# SparkFun_EL_Escudo_Dos.net
KiCad netlist of a schematic drawn in EAGLE
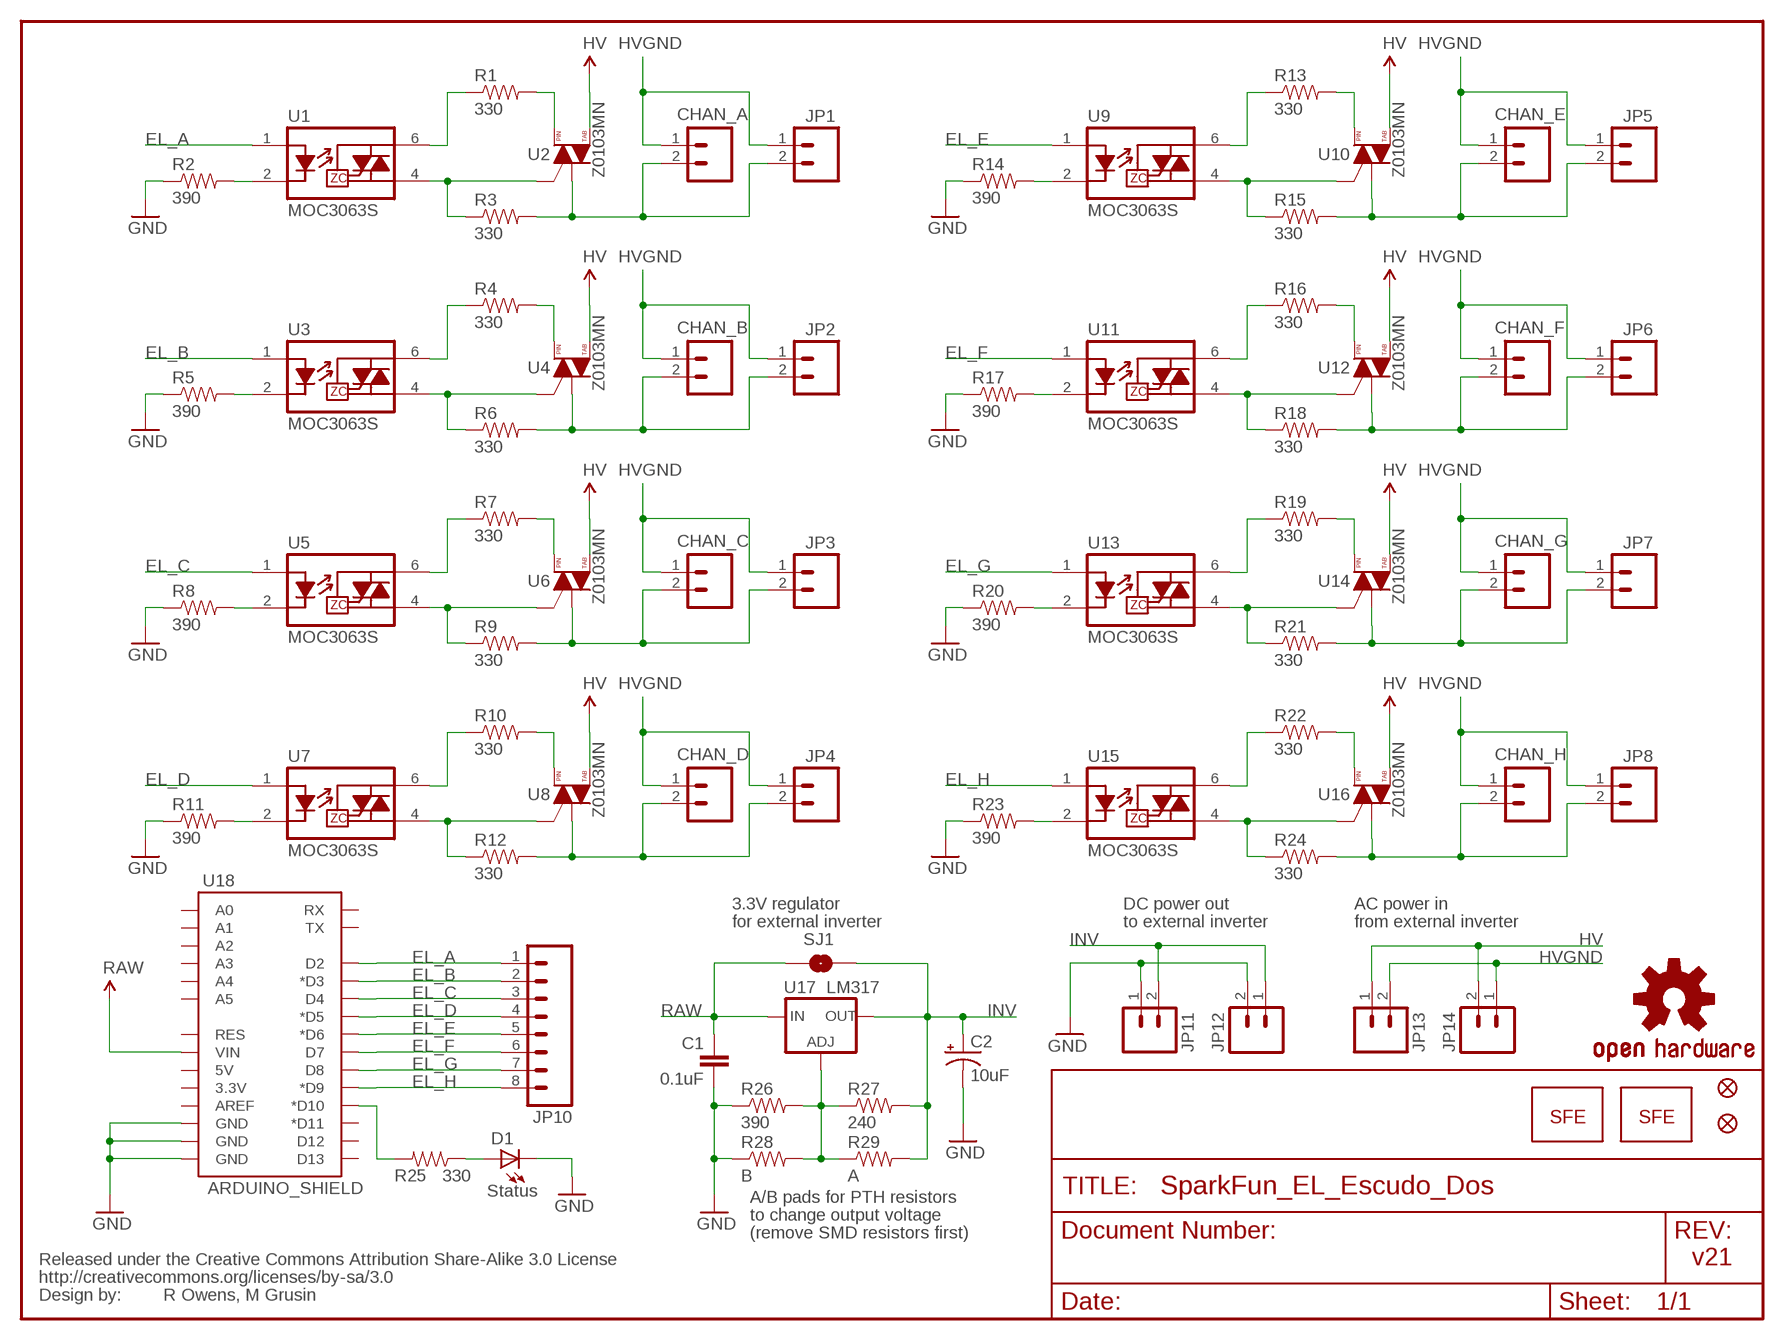
[diagram p0: schematic, sheet 1]

(export (version "E")
  (design (tool "Eeschema 10.0.6"))
  (components
    (comp (ref "C1")
      (value "0.1uF")
      (footprint "eagle-import:0603-CAP")
      (libsource (lib "eagle-import") (part "CAP0603-CAP"))
    )
    (comp (ref "C2")
      (value "10uF")
      (footprint "eagle-import:EIA3216")
      (libsource (lib "eagle-import") (part "CAP_POL1206"))
    )
    (comp (ref "CHAN_A")
      (value "M02-JST-2MM-SMT")
      (footprint "eagle-import:JST-2-SMD")
      (libsource (lib "eagle-import") (part "M02-JST-2MM-SMT"))
    )
    (comp (ref "CHAN_B")
      (value "M02-JST-2MM-SMT")
      (footprint "eagle-import:JST-2-SMD")
      (libsource (lib "eagle-import") (part "M02-JST-2MM-SMT"))
    )
    (comp (ref "CHAN_C")
      (value "M02-JST-2MM-SMT")
      (footprint "eagle-import:JST-2-SMD")
      (libsource (lib "eagle-import") (part "M02-JST-2MM-SMT"))
    )
    (comp (ref "CHAN_D")
      (value "M02-JST-2MM-SMT")
      (footprint "eagle-import:JST-2-SMD")
      (libsource (lib "eagle-import") (part "M02-JST-2MM-SMT"))
    )
    (comp (ref "CHAN_E")
      (value "M02-JST-2MM-SMT")
      (footprint "eagle-import:JST-2-SMD")
      (libsource (lib "eagle-import") (part "M02-JST-2MM-SMT"))
    )
    (comp (ref "CHAN_F")
      (value "M02-JST-2MM-SMT")
      (footprint "eagle-import:JST-2-SMD")
      (libsource (lib "eagle-import") (part "M02-JST-2MM-SMT"))
    )
    (comp (ref "CHAN_G")
      (value "M02-JST-2MM-SMT")
      (footprint "eagle-import:JST-2-SMD")
      (libsource (lib "eagle-import") (part "M02-JST-2MM-SMT"))
    )
    (comp (ref "CHAN_H")
      (value "M02-JST-2MM-SMT")
      (footprint "eagle-import:JST-2-SMD")
      (libsource (lib "eagle-import") (part "M02-JST-2MM-SMT"))
    )
    (comp (ref "D1")
      (value "Status")
      (footprint "eagle-import:LED-0603")
      (libsource (lib "eagle-import") (part "LED0603"))
    )
    (comp (ref "JP1")
      (value "M02PTH")
      (footprint "eagle-import:1X02")
      (libsource (lib "eagle-import") (part "M02PTH"))
    )
    (comp (ref "JP2")
      (value "M02PTH")
      (footprint "eagle-import:1X02")
      (libsource (lib "eagle-import") (part "M02PTH"))
    )
    (comp (ref "JP3")
      (value "M02PTH")
      (footprint "eagle-import:1X02")
      (libsource (lib "eagle-import") (part "M02PTH"))
    )
    (comp (ref "JP4")
      (value "M02PTH")
      (footprint "eagle-import:1X02")
      (libsource (lib "eagle-import") (part "M02PTH"))
    )
    (comp (ref "JP5")
      (value "M02PTH")
      (footprint "eagle-import:1X02")
      (libsource (lib "eagle-import") (part "M02PTH"))
    )
    (comp (ref "JP6")
      (value "M02PTH")
      (footprint "eagle-import:1X02")
      (libsource (lib "eagle-import") (part "M02PTH"))
    )
    (comp (ref "JP7")
      (value "M02PTH")
      (footprint "eagle-import:1X02")
      (libsource (lib "eagle-import") (part "M02PTH"))
    )
    (comp (ref "JP8")
      (value "M02PTH")
      (footprint "eagle-import:1X02")
      (libsource (lib "eagle-import") (part "M02PTH"))
    )
    (comp (ref "JP9")
      (value "LOGO-SFENEW")
      (footprint "eagle-import:SFE-NEW-WEBLOGO")
      (libsource (lib "eagle-import") (part "LOGO-SFENEW"))
    )
    (comp (ref "JP10")
      (value "M081X08")
      (footprint "eagle-import:1X08")
      (libsource (lib "eagle-import") (part "M081X08"))
    )
    (comp (ref "JP11")
      (value "M02-JST-2MM-SMT")
      (footprint "eagle-import:JST-2-SMD")
      (libsource (lib "eagle-import") (part "M02-JST-2MM-SMT"))
    )
    (comp (ref "JP12")
      (value "M02PTH")
      (footprint "eagle-import:1X02")
      (libsource (lib "eagle-import") (part "M02PTH"))
    )
    (comp (ref "JP13")
      (value "M02PTH")
      (footprint "eagle-import:1X02")
      (libsource (lib "eagle-import") (part "M02PTH"))
    )
    (comp (ref "JP14")
      (value "M02-JST-2MM-SMT")
      (footprint "eagle-import:JST-2-SMD")
      (libsource (lib "eagle-import") (part "M02-JST-2MM-SMT"))
    )
    (comp (ref "JP15")
      (value "LOGO-SFENEW")
      (footprint "eagle-import:SFE-NEW-WEBLOGO")
      (libsource (lib "eagle-import") (part "LOGO-SFENEW"))
    )
    (comp (ref "JP16")
      (value "FIDUCIALUFIDUCIAL")
      (footprint "eagle-import:MICRO-FIDUCIAL")
      (libsource (lib "eagle-import") (part "FIDUCIALUFIDUCIAL"))
    )
    (comp (ref "JP17")
      (value "FIDUCIALUFIDUCIAL")
      (footprint "eagle-import:MICRO-FIDUCIAL")
      (libsource (lib "eagle-import") (part "FIDUCIALUFIDUCIAL"))
    )
    (comp (ref "R1")
      (value "330")
      (footprint "eagle-import:0603-RES")
      (libsource (lib "eagle-import") (part "RESISTOR0603-RES"))
    )
    (comp (ref "R2")
      (value "390")
      (footprint "eagle-import:0603-RES")
      (libsource (lib "eagle-import") (part "RESISTOR0603-RES"))
    )
    (comp (ref "R3")
      (value "330")
      (footprint "eagle-import:0603-RES")
      (libsource (lib "eagle-import") (part "RESISTOR0603-RES"))
    )
    (comp (ref "R4")
      (value "330")
      (footprint "eagle-import:0603-RES")
      (libsource (lib "eagle-import") (part "RESISTOR0603-RES"))
    )
    (comp (ref "R5")
      (value "390")
      (footprint "eagle-import:0603-RES")
      (libsource (lib "eagle-import") (part "RESISTOR0603-RES"))
    )
    (comp (ref "R6")
      (value "330")
      (footprint "eagle-import:0603-RES")
      (libsource (lib "eagle-import") (part "RESISTOR0603-RES"))
    )
    (comp (ref "R7")
      (value "330")
      (footprint "eagle-import:0603-RES")
      (libsource (lib "eagle-import") (part "RESISTOR0603-RES"))
    )
    (comp (ref "R8")
      (value "390")
      (footprint "eagle-import:0603-RES")
      (libsource (lib "eagle-import") (part "RESISTOR0603-RES"))
    )
    (comp (ref "R9")
      (value "330")
      (footprint "eagle-import:0603-RES")
      (libsource (lib "eagle-import") (part "RESISTOR0603-RES"))
    )
    (comp (ref "R10")
      (value "330")
      (footprint "eagle-import:0603-RES")
      (libsource (lib "eagle-import") (part "RESISTOR0603-RES"))
    )
    (comp (ref "R11")
      (value "390")
      (footprint "eagle-import:0603-RES")
      (libsource (lib "eagle-import") (part "RESISTOR0603-RES"))
    )
    (comp (ref "R12")
      (value "330")
      (footprint "eagle-import:0603-RES")
      (libsource (lib "eagle-import") (part "RESISTOR0603-RES"))
    )
    (comp (ref "R13")
      (value "330")
      (footprint "eagle-import:0603-RES")
      (libsource (lib "eagle-import") (part "RESISTOR0603-RES"))
    )
    (comp (ref "R14")
      (value "390")
      (footprint "eagle-import:0603-RES")
      (libsource (lib "eagle-import") (part "RESISTOR0603-RES"))
    )
    (comp (ref "R15")
      (value "330")
      (footprint "eagle-import:0603-RES")
      (libsource (lib "eagle-import") (part "RESISTOR0603-RES"))
    )
    (comp (ref "R16")
      (value "330")
      (footprint "eagle-import:0603-RES")
      (libsource (lib "eagle-import") (part "RESISTOR0603-RES"))
    )
    (comp (ref "R17")
      (value "390")
      (footprint "eagle-import:0603-RES")
      (libsource (lib "eagle-import") (part "RESISTOR0603-RES"))
    )
    (comp (ref "R18")
      (value "330")
      (footprint "eagle-import:0603-RES")
      (libsource (lib "eagle-import") (part "RESISTOR0603-RES"))
    )
    (comp (ref "R19")
      (value "330")
      (footprint "eagle-import:0603-RES")
      (libsource (lib "eagle-import") (part "RESISTOR0603-RES"))
    )
    (comp (ref "R20")
      (value "390")
      (footprint "eagle-import:0603-RES")
      (libsource (lib "eagle-import") (part "RESISTOR0603-RES"))
    )
    (comp (ref "R21")
      (value "330")
      (footprint "eagle-import:0603-RES")
      (libsource (lib "eagle-import") (part "RESISTOR0603-RES"))
    )
    (comp (ref "R22")
      (value "330")
      (footprint "eagle-import:0603-RES")
      (libsource (lib "eagle-import") (part "RESISTOR0603-RES"))
    )
    (comp (ref "R23")
      (value "390")
      (footprint "eagle-import:0603-RES")
      (libsource (lib "eagle-import") (part "RESISTOR0603-RES"))
    )
    (comp (ref "R24")
      (value "330")
      (footprint "eagle-import:0603-RES")
      (libsource (lib "eagle-import") (part "RESISTOR0603-RES"))
    )
    (comp (ref "R25")
      (value "330")
      (footprint "eagle-import:0603-RES")
      (libsource (lib "eagle-import") (part "RESISTOR0603-RES"))
    )
    (comp (ref "R26")
      (value "390")
      (footprint "eagle-import:0603-RES")
      (libsource (lib "eagle-import") (part "RESISTOR0603-RES"))
    )
    (comp (ref "R27")
      (value "240")
      (footprint "eagle-import:0603-RES")
      (libsource (lib "eagle-import") (part "RESISTOR0603-RES"))
    )
    (comp (ref "R28")
      (value "B")
      (footprint "eagle-import:AXIAL-0.4")
      (libsource (lib "eagle-import") (part "RESISTORPTH-1/4W"))
    )
    (comp (ref "R29")
      (value "A")
      (footprint "eagle-import:AXIAL-0.4")
      (libsource (lib "eagle-import") (part "RESISTORPTH-1/4W"))
    )
    (comp (ref "SJ1")
      (value "SOLDERJUMPERNO")
      (footprint "eagle-import:SJ_2S-NO")
      (libsource (lib "eagle-import") (part "SOLDERJUMPERNO"))
    )
    (comp (ref "U$4")
      (value "CREATIVE_COMMONS")
      (footprint "eagle-import:CREATIVE_COMMONS")
      (libsource (lib "eagle-import") (part "CREATIVE_COMMONS"))
    )
    (comp (ref "U$5")
      (value "OSHW-LOGOS")
      (footprint "eagle-import:OSHW-LOGO-S")
      (libsource (lib "eagle-import") (part "OSHW-LOGOS"))
    )
    (comp (ref "U1")
      (value "MOC3063S")
      (footprint "eagle-import:DIP8SMD")
      (libsource (lib "eagle-import") (part "MOC3063S"))
    )
    (comp (ref "U2")
      (value "Z0103MN")
      (footprint "eagle-import:SOT223")
      (libsource (lib "eagle-import") (part "TRIACSMD"))
    )
    (comp (ref "U3")
      (value "MOC3063S")
      (footprint "eagle-import:DIP8SMD")
      (libsource (lib "eagle-import") (part "MOC3063S"))
    )
    (comp (ref "U4")
      (value "Z0103MN")
      (footprint "eagle-import:SOT223")
      (libsource (lib "eagle-import") (part "TRIACSMD"))
    )
    (comp (ref "U5")
      (value "MOC3063S")
      (footprint "eagle-import:DIP8SMD")
      (libsource (lib "eagle-import") (part "MOC3063S"))
    )
    (comp (ref "U6")
      (value "Z0103MN")
      (footprint "eagle-import:SOT223")
      (libsource (lib "eagle-import") (part "TRIACSMD"))
    )
    (comp (ref "U7")
      (value "MOC3063S")
      (footprint "eagle-import:DIP8SMD")
      (libsource (lib "eagle-import") (part "MOC3063S"))
    )
    (comp (ref "U8")
      (value "Z0103MN")
      (footprint "eagle-import:SOT223")
      (libsource (lib "eagle-import") (part "TRIACSMD"))
    )
    (comp (ref "U9")
      (value "MOC3063S")
      (footprint "eagle-import:DIP8SMD")
      (libsource (lib "eagle-import") (part "MOC3063S"))
    )
    (comp (ref "U10")
      (value "Z0103MN")
      (footprint "eagle-import:SOT223")
      (libsource (lib "eagle-import") (part "TRIACSMD"))
    )
    (comp (ref "U11")
      (value "MOC3063S")
      (footprint "eagle-import:DIP8SMD")
      (libsource (lib "eagle-import") (part "MOC3063S"))
    )
    (comp (ref "U12")
      (value "Z0103MN")
      (footprint "eagle-import:SOT223")
      (libsource (lib "eagle-import") (part "TRIACSMD"))
    )
    (comp (ref "U13")
      (value "MOC3063S")
      (footprint "eagle-import:DIP8SMD")
      (libsource (lib "eagle-import") (part "MOC3063S"))
    )
    (comp (ref "U14")
      (value "Z0103MN")
      (footprint "eagle-import:SOT223")
      (libsource (lib "eagle-import") (part "TRIACSMD"))
    )
    (comp (ref "U15")
      (value "MOC3063S")
      (footprint "eagle-import:DIP8SMD")
      (libsource (lib "eagle-import") (part "MOC3063S"))
    )
    (comp (ref "U16")
      (value "Z0103MN")
      (footprint "eagle-import:SOT223")
      (libsource (lib "eagle-import") (part "TRIACSMD"))
    )
    (comp (ref "U17")
      (value "LM317")
      (footprint "eagle-import:V-REG_DPACK")
      (libsource (lib "eagle-import") (part "V_REG_317DPACK"))
    )
    (comp (ref "U18")
      (value "ARDUINO_SHIELD")
      (footprint "eagle-import:DUEMILANOVE_SHIELD_NOLABELS")
      (libsource (lib "eagle-import") (part "ARDUINO_SHIELDNOLABELS"))
    )
  )
  (nets
    (net (code "1") (name "/EL_A") (class "Default")
      (node (ref "JP10") (pin "1") (pinfunction "1_1") (pintype "passive"))
      (node (ref "U1") (pin "1") (pinfunction "A_1") (pintype "bidirectional"))
      (node (ref "U18") (pin "D2") (pinfunction "D2_D2") (pintype "bidirectional"))
    )
    (net (code "2") (name "/EL_B") (class "Default")
      (node (ref "JP10") (pin "2") (pinfunction "2_2") (pintype "passive"))
      (node (ref "U18") (pin "D3") (pinfunction "*D3_D3") (pintype "bidirectional"))
      (node (ref "U3") (pin "1") (pinfunction "A_1") (pintype "bidirectional"))
    )
    (net (code "3") (name "/EL_C") (class "Default")
      (node (ref "JP10") (pin "3") (pinfunction "3_3") (pintype "passive"))
      (node (ref "U18") (pin "D4") (pinfunction "D4_D4") (pintype "bidirectional"))
      (node (ref "U5") (pin "1") (pinfunction "A_1") (pintype "bidirectional"))
    )
    (net (code "4") (name "/EL_D") (class "Default")
      (node (ref "JP10") (pin "4") (pinfunction "4_4") (pintype "passive"))
      (node (ref "U18") (pin "D5") (pinfunction "*D5_D5") (pintype "bidirectional"))
      (node (ref "U7") (pin "1") (pinfunction "A_1") (pintype "bidirectional"))
    )
    (net (code "5") (name "/EL_E") (class "Default")
      (node (ref "JP10") (pin "5") (pinfunction "5_5") (pintype "passive"))
      (node (ref "U18") (pin "D6") (pinfunction "*D6_D6") (pintype "bidirectional"))
      (node (ref "U9") (pin "1") (pinfunction "A_1") (pintype "bidirectional"))
    )
    (net (code "6") (name "/EL_F") (class "Default")
      (node (ref "JP10") (pin "6") (pinfunction "6_6") (pintype "passive"))
      (node (ref "U11") (pin "1") (pinfunction "A_1") (pintype "bidirectional"))
      (node (ref "U18") (pin "D7") (pinfunction "D7_D7") (pintype "bidirectional"))
    )
    (net (code "7") (name "/EL_G") (class "Default")
      (node (ref "JP10") (pin "7") (pinfunction "7_7") (pintype "passive"))
      (node (ref "U13") (pin "1") (pinfunction "A_1") (pintype "bidirectional"))
      (node (ref "U18") (pin "D8") (pinfunction "D8_D8") (pintype "bidirectional"))
    )
    (net (code "8") (name "/EL_H") (class "Default")
      (node (ref "JP10") (pin "8") (pinfunction "8_8") (pintype "passive"))
      (node (ref "U15") (pin "1") (pinfunction "A_1") (pintype "bidirectional"))
      (node (ref "U18") (pin "D9") (pinfunction "*D9_D9") (pintype "bidirectional"))
    )
    (net (code "9") (name "/HVGND") (class "Default")
      (node (ref "CHAN_A") (pin "1") (pinfunction "1_1") (pintype "passive"))
      (node (ref "CHAN_B") (pin "1") (pinfunction "1_1") (pintype "passive"))
      (node (ref "CHAN_C") (pin "1") (pinfunction "1_1") (pintype "passive"))
      (node (ref "CHAN_D") (pin "1") (pinfunction "1_1") (pintype "passive"))
      (node (ref "CHAN_E") (pin "1") (pinfunction "1_1") (pintype "passive"))
      (node (ref "CHAN_F") (pin "1") (pinfunction "1_1") (pintype "passive"))
      (node (ref "CHAN_G") (pin "1") (pinfunction "1_1") (pintype "passive"))
      (node (ref "CHAN_H") (pin "1") (pinfunction "1_1") (pintype "passive"))
      (node (ref "JP1") (pin "1") (pinfunction "1_1") (pintype "passive"))
      (node (ref "JP13") (pin "2") (pinfunction "2_2") (pintype "passive"))
      (node (ref "JP14") (pin "1") (pinfunction "1_1") (pintype "passive"))
      (node (ref "JP2") (pin "1") (pinfunction "1_1") (pintype "passive"))
      (node (ref "JP3") (pin "1") (pinfunction "1_1") (pintype "passive"))
      (node (ref "JP4") (pin "1") (pinfunction "1_1") (pintype "passive"))
      (node (ref "JP5") (pin "1") (pinfunction "1_1") (pintype "passive"))
      (node (ref "JP6") (pin "1") (pinfunction "1_1") (pintype "passive"))
      (node (ref "JP7") (pin "1") (pinfunction "1_1") (pintype "passive"))
      (node (ref "JP8") (pin "1") (pinfunction "1_1") (pintype "passive"))
    )
    (net (code "10") (name "/INV") (class "Default")
      (node (ref "C2") (pin "A") (pinfunction "+_A") (pintype "passive"))
      (node (ref "JP11") (pin "2") (pinfunction "2_2") (pintype "passive"))
      (node (ref "JP12") (pin "1") (pinfunction "1_1") (pintype "passive"))
      (node (ref "R27") (pin "2") (pinfunction "2_2") (pintype "passive"))
      (node (ref "R29") (pin "P$2") (pinfunction "2_P$2") (pintype "passive"))
      (node (ref "SJ1") (pin "2") (pinfunction "2_2") (pintype "passive"))
      (node (ref "U17") (pin "4") (pinfunction "OUT_4") (pintype "output"))
    )
    (net (code "11") (name "GND") (class "Default")
      (node (ref "C1") (pin "2") (pinfunction "2_2") (pintype "passive"))
      (node (ref "C2") (pin "C") (pinfunction "-_C") (pintype "passive"))
      (node (ref "D1") (pin "C") (pinfunction "C_C") (pintype "passive"))
      (node (ref "JP11") (pin "1") (pinfunction "1_1") (pintype "passive"))
      (node (ref "JP12") (pin "2") (pinfunction "2_2") (pintype "passive"))
      (node (ref "R11") (pin "1") (pinfunction "1_1") (pintype "passive"))
      (node (ref "R14") (pin "1") (pinfunction "1_1") (pintype "passive"))
      (node (ref "R17") (pin "1") (pinfunction "1_1") (pintype "passive"))
      (node (ref "R2") (pin "1") (pinfunction "1_1") (pintype "passive"))
      (node (ref "R20") (pin "1") (pinfunction "1_1") (pintype "passive"))
      (node (ref "R23") (pin "1") (pinfunction "1_1") (pintype "passive"))
      (node (ref "R26") (pin "1") (pinfunction "1_1") (pintype "passive"))
      (node (ref "R28") (pin "P$1") (pinfunction "1_P$1") (pintype "passive"))
      (node (ref "R5") (pin "1") (pinfunction "1_1") (pintype "passive"))
      (node (ref "R8") (pin "1") (pinfunction "1_1") (pintype "passive"))
      (node (ref "U18") (pin "GND@0") (pinfunction "GND_GND@0") (pintype "bidirectional"))
      (node (ref "U18") (pin "GND@1") (pinfunction "GND_GND@1") (pintype "bidirectional"))
      (node (ref "U18") (pin "GND@2") (pinfunction "GND_GND@2") (pintype "bidirectional"))
    )
    (net (code "12") (name "HV") (class "Default")
      (node (ref "JP13") (pin "1") (pinfunction "1_1") (pintype "passive"))
      (node (ref "JP14") (pin "2") (pinfunction "2_2") (pintype "passive"))
      (node (ref "U10") (pin "4") (pinfunction "T2_4") (pintype "passive"))
      (node (ref "U12") (pin "4") (pinfunction "T2_4") (pintype "passive"))
      (node (ref "U14") (pin "4") (pinfunction "T2_4") (pintype "passive"))
      (node (ref "U16") (pin "4") (pinfunction "T2_4") (pintype "passive"))
      (node (ref "U2") (pin "4") (pinfunction "T2_4") (pintype "passive"))
      (node (ref "U4") (pin "4") (pinfunction "T2_4") (pintype "passive"))
      (node (ref "U6") (pin "4") (pinfunction "T2_4") (pintype "passive"))
      (node (ref "U8") (pin "4") (pinfunction "T2_4") (pintype "passive"))
    )
    (net (code "13") (name "Net-(D1-PadA)") (class "Default")
      (node (ref "D1") (pin "A") (pinfunction "A_A") (pintype "passive"))
      (node (ref "R25") (pin "1") (pinfunction "1_1") (pintype "passive"))
    )
    (net (code "14") (name "Net-(R1-Pad2)") (class "Default")
      (node (ref "R1") (pin "2") (pinfunction "2_2") (pintype "passive"))
      (node (ref "U2") (pin "2") (pinfunction "T2_2") (pintype "passive"))
    )
    (net (code "15") (name "Net-(R4-Pad2)") (class "Default")
      (node (ref "R4") (pin "2") (pinfunction "2_2") (pintype "passive"))
      (node (ref "U4") (pin "2") (pinfunction "T2_2") (pintype "passive"))
    )
    (net (code "16") (name "Net-(R7-Pad2)") (class "Default")
      (node (ref "R7") (pin "2") (pinfunction "2_2") (pintype "passive"))
      (node (ref "U6") (pin "2") (pinfunction "T2_2") (pintype "passive"))
    )
    (net (code "17") (name "Net-(R10-Pad2)") (class "Default")
      (node (ref "R10") (pin "2") (pinfunction "2_2") (pintype "passive"))
      (node (ref "U8") (pin "2") (pinfunction "T2_2") (pintype "passive"))
    )
    (net (code "18") (name "Net-(R13-Pad2)") (class "Default")
      (node (ref "R13") (pin "2") (pinfunction "2_2") (pintype "passive"))
      (node (ref "U10") (pin "2") (pinfunction "T2_2") (pintype "passive"))
    )
    (net (code "19") (name "Net-(R16-Pad2)") (class "Default")
      (node (ref "R16") (pin "2") (pinfunction "2_2") (pintype "passive"))
      (node (ref "U12") (pin "2") (pinfunction "T2_2") (pintype "passive"))
    )
    (net (code "20") (name "Net-(R19-Pad2)") (class "Default")
      (node (ref "R19") (pin "2") (pinfunction "2_2") (pintype "passive"))
      (node (ref "U14") (pin "2") (pinfunction "T2_2") (pintype "passive"))
    )
    (net (code "21") (name "Net-(R22-Pad2)") (class "Default")
      (node (ref "R22") (pin "2") (pinfunction "2_2") (pintype "passive"))
      (node (ref "U16") (pin "2") (pinfunction "T2_2") (pintype "passive"))
    )
    (net (code "22") (name "Net-(R28-2)") (class "Default")
      (node (ref "R26") (pin "2") (pinfunction "2_2") (pintype "passive"))
      (node (ref "R27") (pin "1") (pinfunction "1_1") (pintype "passive"))
      (node (ref "R28") (pin "P$2") (pinfunction "2_P$2") (pintype "passive"))
      (node (ref "R29") (pin "P$1") (pinfunction "1_P$1") (pintype "passive"))
      (node (ref "U17") (pin "1") (pinfunction "ADJ_1") (pintype "input"))
    )
    (net (code "23") (name "Net-(U1-K)") (class "Default")
      (node (ref "R2") (pin "2") (pinfunction "2_2") (pintype "passive"))
      (node (ref "U1") (pin "2") (pinfunction "K_2") (pintype "bidirectional"))
    )
    (net (code "24") (name "Net-(U1-T1)") (class "Default")
      (node (ref "R1") (pin "1") (pinfunction "1_1") (pintype "passive"))
      (node (ref "U1") (pin "6") (pinfunction "T1_6") (pintype "bidirectional"))
    )
    (net (code "25") (name "Net-(U1-T2)") (class "Default")
      (node (ref "R3") (pin "1") (pinfunction "1_1") (pintype "passive"))
      (node (ref "U1") (pin "4") (pinfunction "T2_4") (pintype "bidirectional"))
      (node (ref "U2") (pin "3") (pinfunction "G_3") (pintype "bidirectional"))
    )
    (net (code "26") (name "Net-(U2-T1)") (class "Default")
      (node (ref "CHAN_A") (pin "2") (pinfunction "2_2") (pintype "passive"))
      (node (ref "JP1") (pin "2") (pinfunction "2_2") (pintype "passive"))
      (node (ref "R3") (pin "2") (pinfunction "2_2") (pintype "passive"))
      (node (ref "U2") (pin "1") (pinfunction "T1_1") (pintype "bidirectional"))
    )
    (net (code "27") (name "Net-(U3-K)") (class "Default")
      (node (ref "R5") (pin "2") (pinfunction "2_2") (pintype "passive"))
      (node (ref "U3") (pin "2") (pinfunction "K_2") (pintype "bidirectional"))
    )
    (net (code "28") (name "Net-(U3-T1)") (class "Default")
      (node (ref "R4") (pin "1") (pinfunction "1_1") (pintype "passive"))
      (node (ref "U3") (pin "6") (pinfunction "T1_6") (pintype "bidirectional"))
    )
    (net (code "29") (name "Net-(U3-T2)") (class "Default")
      (node (ref "R6") (pin "1") (pinfunction "1_1") (pintype "passive"))
      (node (ref "U3") (pin "4") (pinfunction "T2_4") (pintype "bidirectional"))
      (node (ref "U4") (pin "3") (pinfunction "G_3") (pintype "bidirectional"))
    )
    (net (code "30") (name "Net-(U4-T1)") (class "Default")
      (node (ref "CHAN_B") (pin "2") (pinfunction "2_2") (pintype "passive"))
      (node (ref "JP2") (pin "2") (pinfunction "2_2") (pintype "passive"))
      (node (ref "R6") (pin "2") (pinfunction "2_2") (pintype "passive"))
      (node (ref "U4") (pin "1") (pinfunction "T1_1") (pintype "bidirectional"))
    )
    (net (code "31") (name "Net-(U5-K)") (class "Default")
      (node (ref "R8") (pin "2") (pinfunction "2_2") (pintype "passive"))
      (node (ref "U5") (pin "2") (pinfunction "K_2") (pintype "bidirectional"))
    )
    (net (code "32") (name "Net-(U5-T1)") (class "Default")
      (node (ref "R7") (pin "1") (pinfunction "1_1") (pintype "passive"))
      (node (ref "U5") (pin "6") (pinfunction "T1_6") (pintype "bidirectional"))
    )
    (net (code "33") (name "Net-(U5-T2)") (class "Default")
      (node (ref "R9") (pin "1") (pinfunction "1_1") (pintype "passive"))
      (node (ref "U5") (pin "4") (pinfunction "T2_4") (pintype "bidirectional"))
      (node (ref "U6") (pin "3") (pinfunction "G_3") (pintype "bidirectional"))
    )
    (net (code "34") (name "Net-(U6-T1)") (class "Default")
      (node (ref "CHAN_C") (pin "2") (pinfunction "2_2") (pintype "passive"))
      (node (ref "JP3") (pin "2") (pinfunction "2_2") (pintype "passive"))
      (node (ref "R9") (pin "2") (pinfunction "2_2") (pintype "passive"))
      (node (ref "U6") (pin "1") (pinfunction "T1_1") (pintype "bidirectional"))
    )
    (net (code "35") (name "Net-(U7-K)") (class "Default")
      (node (ref "R11") (pin "2") (pinfunction "2_2") (pintype "passive"))
      (node (ref "U7") (pin "2") (pinfunction "K_2") (pintype "bidirectional"))
    )
    (net (code "36") (name "Net-(U7-T1)") (class "Default")
      (node (ref "R10") (pin "1") (pinfunction "1_1") (pintype "passive"))
      (node (ref "U7") (pin "6") (pinfunction "T1_6") (pintype "bidirectional"))
    )
    (net (code "37") (name "Net-(U7-T2)") (class "Default")
      (node (ref "R12") (pin "1") (pinfunction "1_1") (pintype "passive"))
      (node (ref "U7") (pin "4") (pinfunction "T2_4") (pintype "bidirectional"))
      (node (ref "U8") (pin "3") (pinfunction "G_3") (pintype "bidirectional"))
    )
    (net (code "38") (name "Net-(U8-T1)") (class "Default")
      (node (ref "CHAN_D") (pin "2") (pinfunction "2_2") (pintype "passive"))
      (node (ref "JP4") (pin "2") (pinfunction "2_2") (pintype "passive"))
      (node (ref "R12") (pin "2") (pinfunction "2_2") (pintype "passive"))
      (node (ref "U8") (pin "1") (pinfunction "T1_1") (pintype "bidirectional"))
    )
    (net (code "39") (name "Net-(U9-K)") (class "Default")
      (node (ref "R14") (pin "2") (pinfunction "2_2") (pintype "passive"))
      (node (ref "U9") (pin "2") (pinfunction "K_2") (pintype "bidirectional"))
    )
    (net (code "40") (name "Net-(U9-T1)") (class "Default")
      (node (ref "R13") (pin "1") (pinfunction "1_1") (pintype "passive"))
      (node (ref "U9") (pin "6") (pinfunction "T1_6") (pintype "bidirectional"))
    )
    (net (code "41") (name "Net-(U10-G)") (class "Default")
      (node (ref "R15") (pin "1") (pinfunction "1_1") (pintype "passive"))
      (node (ref "U10") (pin "3") (pinfunction "G_3") (pintype "bidirectional"))
      (node (ref "U9") (pin "4") (pinfunction "T2_4") (pintype "bidirectional"))
    )
    (net (code "42") (name "Net-(U10-T1)") (class "Default")
      (node (ref "CHAN_E") (pin "2") (pinfunction "2_2") (pintype "passive"))
      (node (ref "JP5") (pin "2") (pinfunction "2_2") (pintype "passive"))
      (node (ref "R15") (pin "2") (pinfunction "2_2") (pintype "passive"))
      (node (ref "U10") (pin "1") (pinfunction "T1_1") (pintype "bidirectional"))
    )
    (net (code "43") (name "Net-(U11-K)") (class "Default")
      (node (ref "R17") (pin "2") (pinfunction "2_2") (pintype "passive"))
      (node (ref "U11") (pin "2") (pinfunction "K_2") (pintype "bidirectional"))
    )
    (net (code "44") (name "Net-(U11-T1)") (class "Default")
      (node (ref "R16") (pin "1") (pinfunction "1_1") (pintype "passive"))
      (node (ref "U11") (pin "6") (pinfunction "T1_6") (pintype "bidirectional"))
    )
    (net (code "45") (name "Net-(U11-T2)") (class "Default")
      (node (ref "R18") (pin "1") (pinfunction "1_1") (pintype "passive"))
      (node (ref "U11") (pin "4") (pinfunction "T2_4") (pintype "bidirectional"))
      (node (ref "U12") (pin "3") (pinfunction "G_3") (pintype "bidirectional"))
    )
    (net (code "46") (name "Net-(U12-T1)") (class "Default")
      (node (ref "CHAN_F") (pin "2") (pinfunction "2_2") (pintype "passive"))
      (node (ref "JP6") (pin "2") (pinfunction "2_2") (pintype "passive"))
      (node (ref "R18") (pin "2") (pinfunction "2_2") (pintype "passive"))
      (node (ref "U12") (pin "1") (pinfunction "T1_1") (pintype "bidirectional"))
    )
    (net (code "47") (name "Net-(U13-K)") (class "Default")
      (node (ref "R20") (pin "2") (pinfunction "2_2") (pintype "passive"))
      (node (ref "U13") (pin "2") (pinfunction "K_2") (pintype "bidirectional"))
    )
    (net (code "48") (name "Net-(U13-T1)") (class "Default")
      (node (ref "R19") (pin "1") (pinfunction "1_1") (pintype "passive"))
      (node (ref "U13") (pin "6") (pinfunction "T1_6") (pintype "bidirectional"))
    )
    (net (code "49") (name "Net-(U13-T2)") (class "Default")
      (node (ref "R21") (pin "1") (pinfunction "1_1") (pintype "passive"))
      (node (ref "U13") (pin "4") (pinfunction "T2_4") (pintype "bidirectional"))
      (node (ref "U14") (pin "3") (pinfunction "G_3") (pintype "bidirectional"))
    )
    (net (code "50") (name "Net-(U14-T1)") (class "Default")
      (node (ref "CHAN_G") (pin "2") (pinfunction "2_2") (pintype "passive"))
      (node (ref "JP7") (pin "2") (pinfunction "2_2") (pintype "passive"))
      (node (ref "R21") (pin "2") (pinfunction "2_2") (pintype "passive"))
      (node (ref "U14") (pin "1") (pinfunction "T1_1") (pintype "bidirectional"))
    )
    (net (code "51") (name "Net-(U15-K)") (class "Default")
      (node (ref "R23") (pin "2") (pinfunction "2_2") (pintype "passive"))
      (node (ref "U15") (pin "2") (pinfunction "K_2") (pintype "bidirectional"))
    )
    (net (code "52") (name "Net-(U15-T1)") (class "Default")
      (node (ref "R22") (pin "1") (pinfunction "1_1") (pintype "passive"))
      (node (ref "U15") (pin "6") (pinfunction "T1_6") (pintype "bidirectional"))
    )
    (net (code "53") (name "Net-(U15-T2)") (class "Default")
      (node (ref "R24") (pin "1") (pinfunction "1_1") (pintype "passive"))
      (node (ref "U15") (pin "4") (pinfunction "T2_4") (pintype "bidirectional"))
      (node (ref "U16") (pin "3") (pinfunction "G_3") (pintype "bidirectional"))
    )
    (net (code "54") (name "Net-(U16-T1)") (class "Default")
      (node (ref "CHAN_H") (pin "2") (pinfunction "2_2") (pintype "passive"))
      (node (ref "JP8") (pin "2") (pinfunction "2_2") (pintype "passive"))
      (node (ref "R24") (pin "2") (pinfunction "2_2") (pintype "passive"))
      (node (ref "U16") (pin "1") (pinfunction "T1_1") (pintype "bidirectional"))
    )
    (net (code "55") (name "Net-(U18-*D10)") (class "Default")
      (node (ref "R25") (pin "2") (pinfunction "2_2") (pintype "passive"))
      (node (ref "U18") (pin "D10") (pinfunction "*D10_D10") (pintype "bidirectional"))
    )
    (net (code "56") (name "RAW") (class "Default")
      (node (ref "C1") (pin "1") (pinfunction "1_1") (pintype "passive"))
      (node (ref "SJ1") (pin "1") (pinfunction "1_1") (pintype "passive"))
      (node (ref "U17") (pin "3") (pinfunction "IN_3") (pintype "input"))
      (node (ref "U18") (pin "VIN") (pinfunction "VIN_VIN") (pintype "bidirectional"))
    )
    (net (code "57") (name "unconnected-(U18-*D11-PadD11)") (class "Default")
      (node (ref "U18") (pin "D11") (pinfunction "*D11_D11") (pintype "bidirectional"))
    )
    (net (code "58") (name "unconnected-(U18-Pad3.3V)") (class "Default")
      (node (ref "U18") (pin "3.3V") (pinfunction "3.3V_3.3V") (pintype "bidirectional"))
    )
    (net (code "59") (name "unconnected-(U18-Pad5V)") (class "Default")
      (node (ref "U18") (pin "5V") (pinfunction "5V_5V") (pintype "bidirectional"))
    )
    (net (code "60") (name "unconnected-(U18-PadA0)") (class "Default")
      (node (ref "U18") (pin "A0") (pinfunction "A0_A0") (pintype "bidirectional"))
    )
    (net (code "61") (name "unconnected-(U18-PadA1)") (class "Default")
      (node (ref "U18") (pin "A1") (pinfunction "A1_A1") (pintype "bidirectional"))
    )
    (net (code "62") (name "unconnected-(U18-PadA2)") (class "Default")
      (node (ref "U18") (pin "A2") (pinfunction "A2_A2") (pintype "bidirectional"))
    )
    (net (code "63") (name "unconnected-(U18-PadA3)") (class "Default")
      (node (ref "U18") (pin "A3") (pinfunction "A3_A3") (pintype "bidirectional"))
    )
    (net (code "64") (name "unconnected-(U18-PadA4)") (class "Default")
      (node (ref "U18") (pin "A4") (pinfunction "A4_A4") (pintype "bidirectional"))
    )
    (net (code "65") (name "unconnected-(U18-PadA5)") (class "Default")
      (node (ref "U18") (pin "A5") (pinfunction "A5_A5") (pintype "bidirectional"))
    )
    (net (code "66") (name "unconnected-(U18-PadAREF)") (class "Default")
      (node (ref "U18") (pin "AREF") (pinfunction "AREF_AREF") (pintype "bidirectional"))
    )
    (net (code "67") (name "unconnected-(U18-PadD12)") (class "Default")
      (node (ref "U18") (pin "D12") (pinfunction "D12_D12") (pintype "bidirectional"))
    )
    (net (code "68") (name "unconnected-(U18-PadD13)") (class "Default")
      (node (ref "U18") (pin "D13") (pinfunction "D13_D13") (pintype "bidirectional"))
    )
    (net (code "69") (name "unconnected-(U18-PadRES)") (class "Default")
      (node (ref "U18") (pin "RES") (pinfunction "RES_RES") (pintype "bidirectional"))
    )
    (net (code "70") (name "unconnected-(U18-PadRX)") (class "Default")
      (node (ref "U18") (pin "RX") (pinfunction "RX_RX") (pintype "bidirectional"))
    )
    (net (code "71") (name "unconnected-(U18-PadTX)") (class "Default")
      (node (ref "U18") (pin "TX") (pinfunction "TX_TX") (pintype "bidirectional"))
    )
  )
)
